# 14044-sparkfun-mlx90640-qwiic-breakout-p.net
KiCad netlist of a schematic drawn in EAGLE
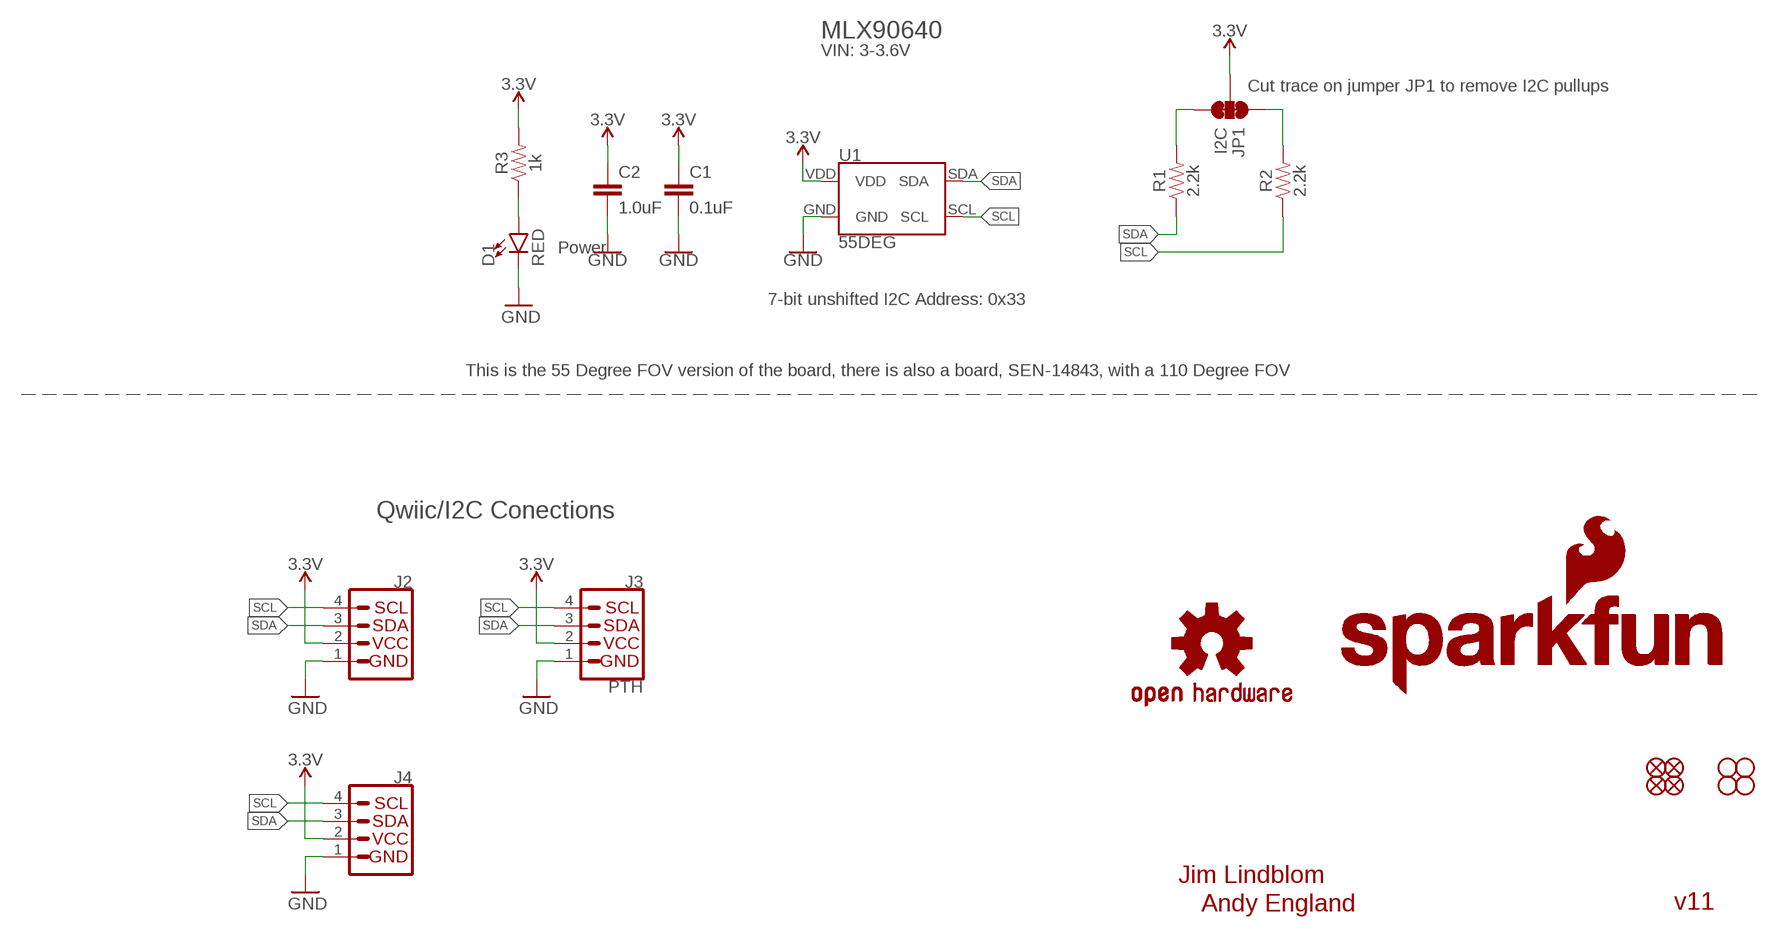
[diagram p0: schematic, sheet 1]

(export (version "E")
  (design (tool "Eeschema 10.0.6"))
  (components
    (comp (ref "C1")
      (value "0.1uF")
      (footprint "eagle-import:0603")
      (libsource (lib "eagle-import") (part "0.1UF-0603-25V-(+80/-20%)"))
    )
    (comp (ref "C2")
      (value "1.0uF")
      (footprint "eagle-import:0603")
      (libsource (lib "eagle-import") (part "1.0UF-0603-16V-10%"))
    )
    (comp (ref "D1")
      (value "RED")
      (footprint "eagle-import:LED-0603")
      (libsource (lib "eagle-import") (part "LED-RED0603"))
    )
    (comp (ref "J2")
      (value "QWIIC_CONNECTORJS-1MM")
      (footprint "eagle-import:1X04_1MM_RA")
      (libsource (lib "eagle-import") (part "QWIIC_CONNECTORJS-1MM"))
    )
    (comp (ref "J3")
      (value "PTH")
      (footprint "eagle-import:1X04_NO_SILK")
      (libsource (lib "eagle-import") (part "I2C_STANDARD_NO_SILK"))
    )
    (comp (ref "J4")
      (value "QWIIC_CONNECTORJS-1MM")
      (footprint "eagle-import:1X04_1MM_RA")
      (libsource (lib "eagle-import") (part "QWIIC_CONNECTORJS-1MM"))
    )
    (comp (ref "JP1")
      (value "I2C")
      (footprint "eagle-import:SMT-JUMPER_3_2-NC_TRACE_NO-SILK")
      (libsource (lib "eagle-import") (part "JUMPER-SMT_3_2-NC_TRACE_NO-SILK"))
    )
    (comp (ref "JP2")
      (value "FIDUCIALUFIDUCIAL")
      (footprint "eagle-import:MICRO-FIDUCIAL")
      (libsource (lib "eagle-import") (part "FIDUCIALUFIDUCIAL"))
    )
    (comp (ref "JP3")
      (value "STAND-OFF")
      (footprint "eagle-import:STAND-OFF")
      (libsource (lib "eagle-import") (part "STAND-OFF"))
    )
    (comp (ref "JP4")
      (value "STAND-OFF")
      (footprint "eagle-import:STAND-OFF")
      (libsource (lib "eagle-import") (part "STAND-OFF"))
    )
    (comp (ref "JP5")
      (value "FIDUCIALUFIDUCIAL")
      (footprint "eagle-import:MICRO-FIDUCIAL")
      (libsource (lib "eagle-import") (part "FIDUCIALUFIDUCIAL"))
    )
    (comp (ref "JP6")
      (value "FIDUCIALUFIDUCIAL")
      (footprint "eagle-import:MICRO-FIDUCIAL")
      (libsource (lib "eagle-import") (part "FIDUCIALUFIDUCIAL"))
    )
    (comp (ref "JP7")
      (value "FIDUCIALUFIDUCIAL")
      (footprint "eagle-import:MICRO-FIDUCIAL")
      (libsource (lib "eagle-import") (part "FIDUCIALUFIDUCIAL"))
    )
    (comp (ref "JP8")
      (value "STAND-OFF")
      (footprint "eagle-import:STAND-OFF")
      (libsource (lib "eagle-import") (part "STAND-OFF"))
    )
    (comp (ref "JP9")
      (value "STAND-OFF")
      (footprint "eagle-import:STAND-OFF")
      (libsource (lib "eagle-import") (part "STAND-OFF"))
    )
    (comp (ref "LOGO1")
      (value "OSHW-LOGOMINI")
      (footprint "eagle-import:OSHW-LOGO-MINI")
      (libsource (lib "eagle-import") (part "OSHW-LOGOMINI"))
    )
    (comp (ref "LOGO2")
      (value "SFE_LOGO_NAME_FLAME.1_INCH")
      (footprint "eagle-import:SFE_LOGO_NAME_FLAME_.1")
      (libsource (lib "eagle-import") (part "SFE_LOGO_NAME_FLAME.1_INCH"))
    )
    (comp (ref "LOGO3")
      (value "SFE_LOGO_NAME.1_INCH")
      (footprint "eagle-import:SFE_LOGO_NAME_.1")
      (libsource (lib "eagle-import") (part "SFE_LOGO_NAME.1_INCH"))
    )
    (comp (ref "R1")
      (value "2.2k")
      (footprint "eagle-import:0603")
      (libsource (lib "eagle-import") (part "2.2KOHM-0603-1/10W-1%"))
    )
    (comp (ref "R2")
      (value "2.2k")
      (footprint "eagle-import:0603")
      (libsource (lib "eagle-import") (part "2.2KOHM-0603-1/10W-1%"))
    )
    (comp (ref "R3")
      (value "1k")
      (footprint "eagle-import:0603")
      (libsource (lib "eagle-import") (part "1KOHM-0603-1/10W-1%"))
    )
    (comp (ref "U1")
      (value "55DEG")
      (footprint "eagle-import:MLX90540_MLX90640")
      (libsource (lib "eagle-import") (part "MLX90540_MLX90640"))
    )
  )
  (nets
    (net (code "1") (name "3.3V") (class "Default")
      (node (ref "C1") (pin "1") (pinfunction "1_1") (pintype "passive"))
      (node (ref "C2") (pin "1") (pinfunction "1_1") (pintype "passive"))
      (node (ref "J2") (pin "2") (pinfunction "2_2") (pintype "power_in"))
      (node (ref "J3") (pin "2") (pinfunction "VCC_2") (pintype "power_in"))
      (node (ref "J4") (pin "2") (pinfunction "2_2") (pintype "power_in"))
      (node (ref "JP1") (pin "2") (pinfunction "2_2") (pintype "passive"))
      (node (ref "R3") (pin "2") (pinfunction "2_2") (pintype "passive"))
      (node (ref "U1") (pin "VDD") (pinfunction "VDD_VDD") (pintype "bidirectional"))
    )
    (net (code "2") (name "GND") (class "Default")
      (node (ref "C1") (pin "2") (pinfunction "2_2") (pintype "passive"))
      (node (ref "C2") (pin "2") (pinfunction "2_2") (pintype "passive"))
      (node (ref "D1") (pin "C") (pinfunction "C_C") (pintype "passive"))
      (node (ref "J2") (pin "1") (pinfunction "1_1") (pintype "power_in"))
      (node (ref "J3") (pin "1") (pinfunction "GND_1") (pintype "power_in"))
      (node (ref "J4") (pin "1") (pinfunction "1_1") (pintype "power_in"))
      (node (ref "U1") (pin "GND") (pinfunction "GND_GND") (pintype "bidirectional"))
    )
    (net (code "3") (name "Net-(D1-PadA)") (class "Default")
      (node (ref "D1") (pin "A") (pinfunction "A_A") (pintype "passive"))
      (node (ref "R3") (pin "1") (pinfunction "1_1") (pintype "passive"))
    )
    (net (code "4") (name "Net-(JP1-Pad1)") (class "Default")
      (node (ref "JP1") (pin "1") (pinfunction "1_1") (pintype "passive"))
      (node (ref "R2") (pin "2") (pinfunction "2_2") (pintype "passive"))
    )
    (net (code "5") (name "Net-(JP1-Pad3)") (class "Default")
      (node (ref "JP1") (pin "3") (pinfunction "3_3") (pintype "passive"))
      (node (ref "R1") (pin "2") (pinfunction "2_2") (pintype "passive"))
    )
    (net (code "6") (name "SCL") (class "Default")
      (node (ref "J2") (pin "4") (pinfunction "4_4") (pintype "passive"))
      (node (ref "J3") (pin "4") (pinfunction "SCL_4") (pintype "passive"))
      (node (ref "J4") (pin "4") (pinfunction "4_4") (pintype "passive"))
      (node (ref "R2") (pin "1") (pinfunction "1_1") (pintype "passive"))
      (node (ref "U1") (pin "SCL") (pinfunction "SCL_SCL") (pintype "bidirectional"))
    )
    (net (code "7") (name "SDA") (class "Default")
      (node (ref "J2") (pin "3") (pinfunction "3_3") (pintype "passive"))
      (node (ref "J3") (pin "3") (pinfunction "SDA_3") (pintype "passive"))
      (node (ref "J4") (pin "3") (pinfunction "3_3") (pintype "passive"))
      (node (ref "R1") (pin "1") (pinfunction "1_1") (pintype "passive"))
      (node (ref "U1") (pin "SDA") (pinfunction "SDA_SDA") (pintype "bidirectional"))
    )
  )
)
